# SCH_usb-usb_2025-03-20.net
KiCad netlist of a schematic drawn in EasyEDA
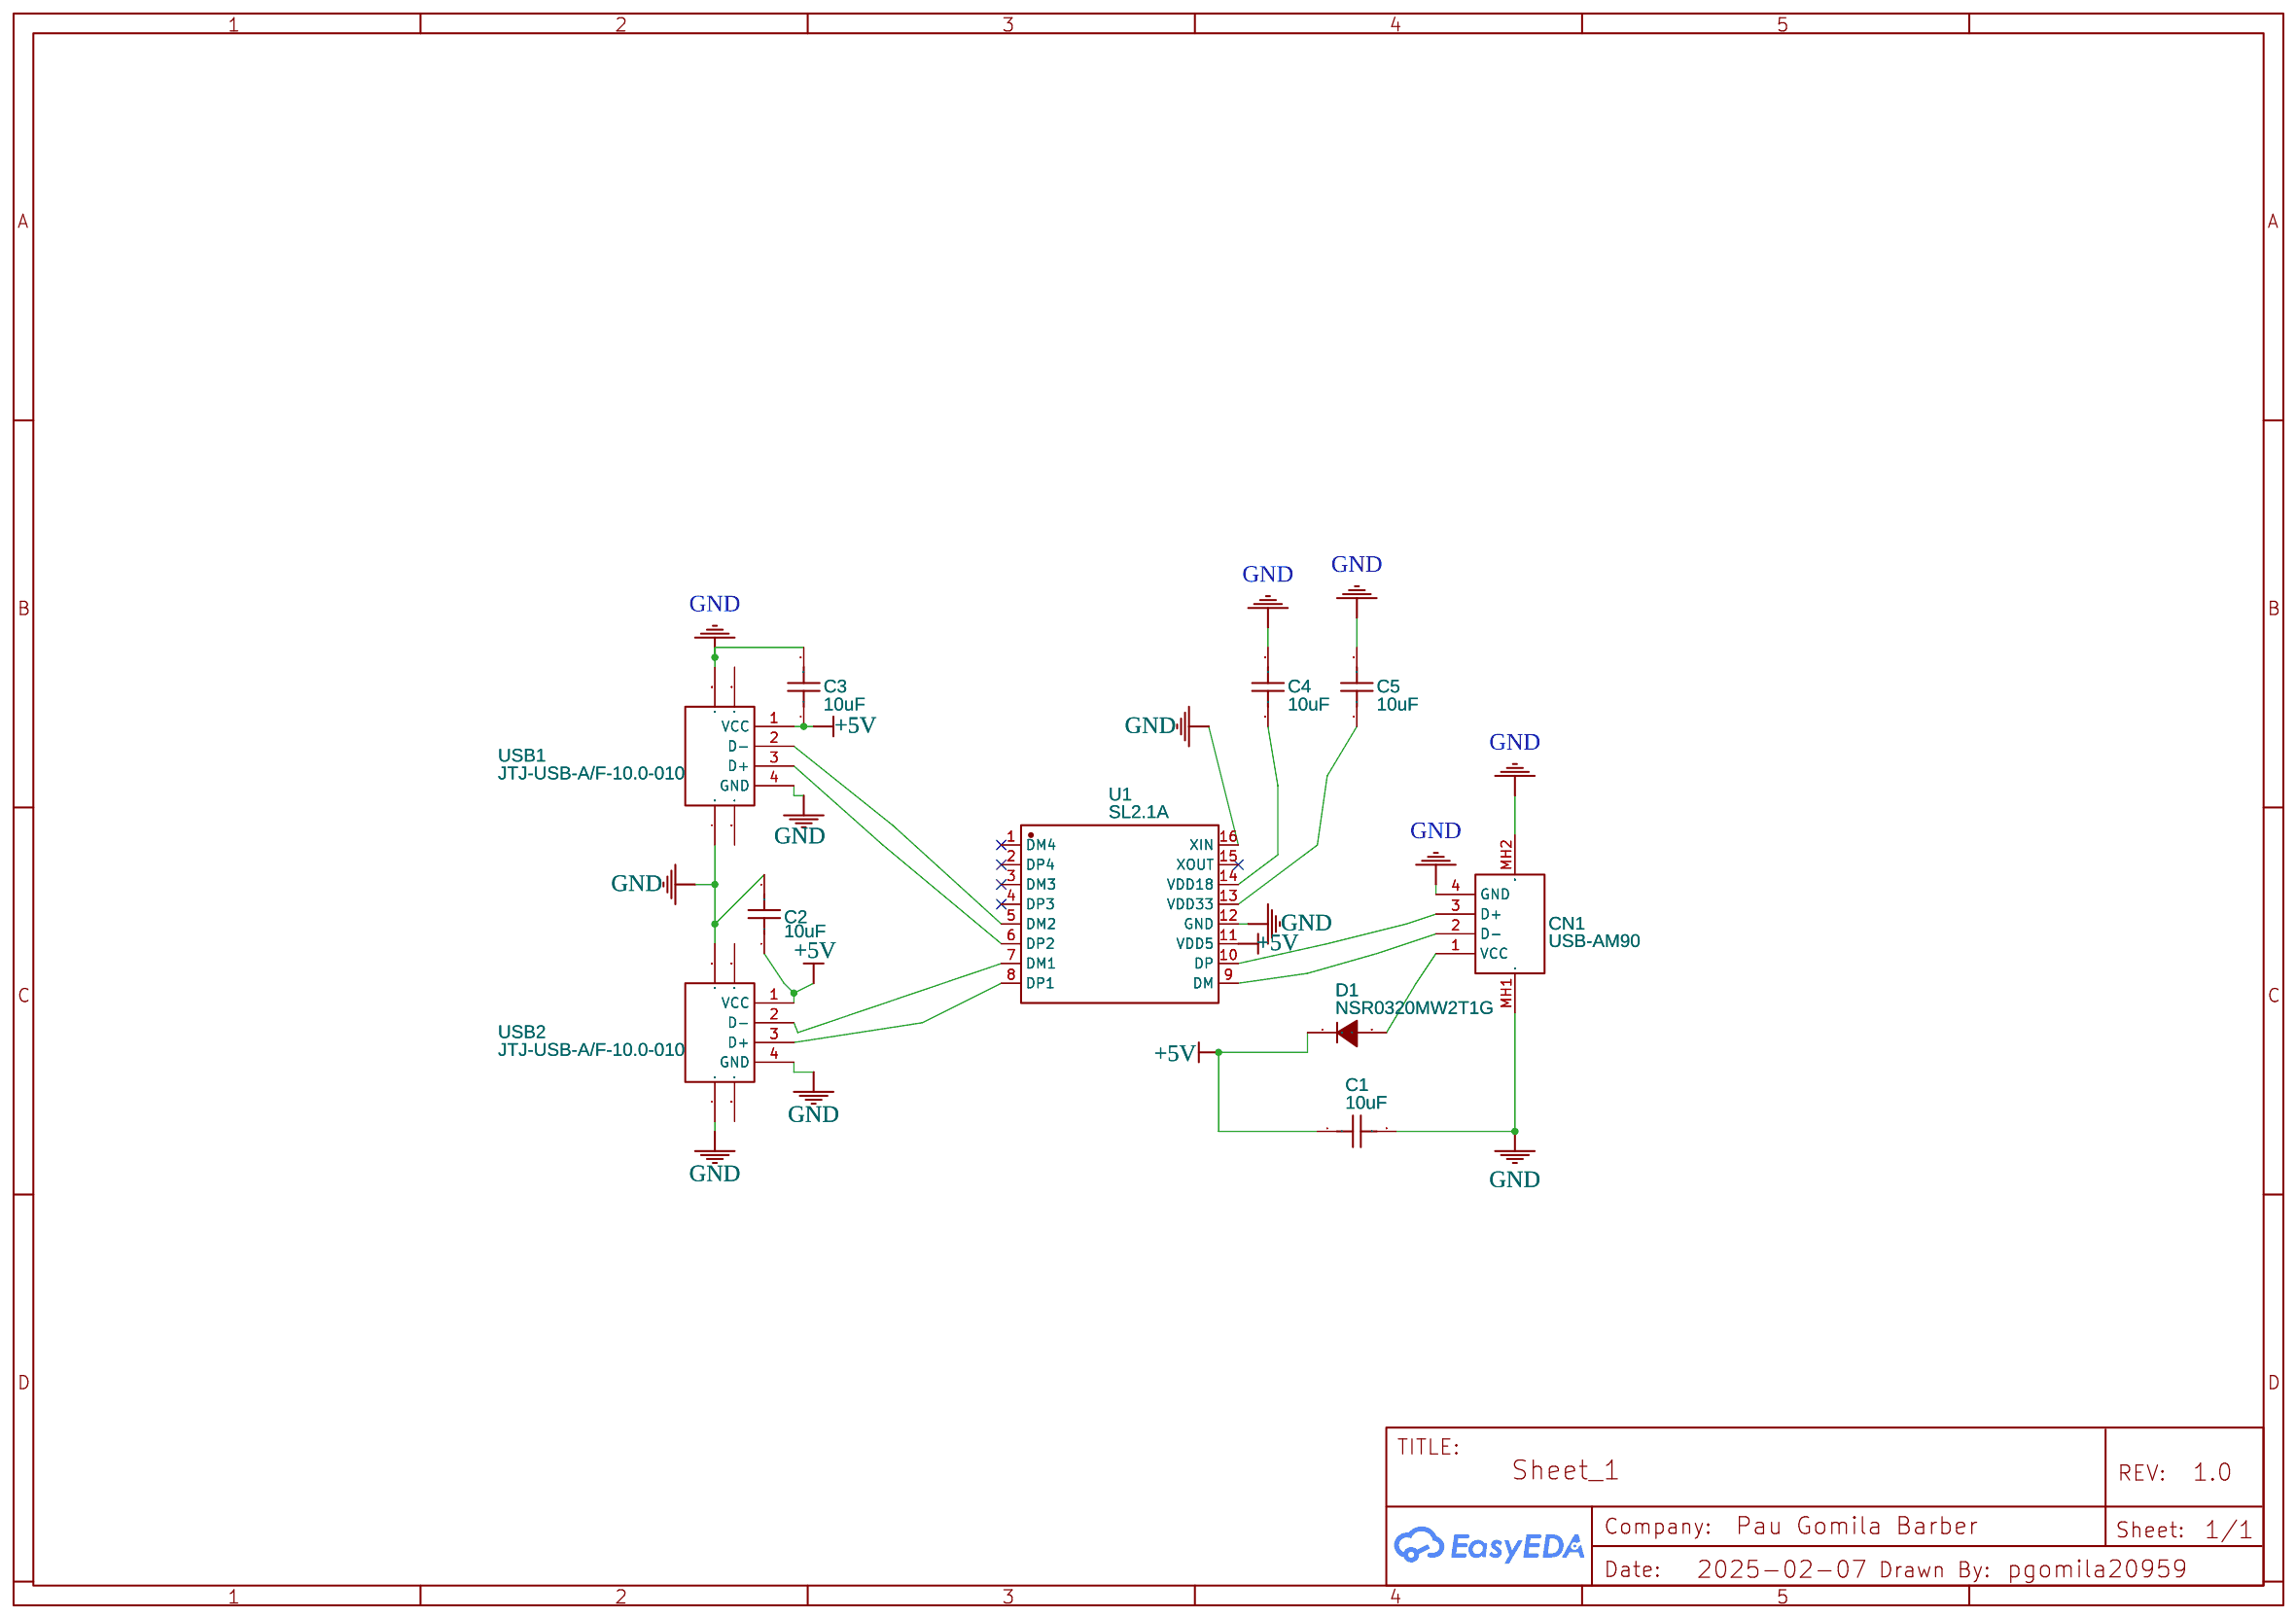
[diagram p0: schematic sheet]

(export (version "E")
  (design (tool "Eeschema 10.0.6"))
  (components
    (comp (ref "C1")
      (value "10uF")
      (fields
        (field (name "Manufacturer Part") "CL10A106KP8NNNC")
        (field (name "Manufacturer") "SAMSUNG(三星)")
      )
      (libsource (lib "") (part "CL10A106KP8NNNC_1"))
    )
    (comp (ref "C2")
      (value "10uF")
      (fields
        (field (name "Manufacturer Part") "CL10A106KP8NNNC")
        (field (name "Manufacturer") "SAMSUNG(三星)")
      )
      (libsource (lib "") (part "CL10A106KP8NNNC"))
    )
    (comp (ref "C3")
      (value "10uF")
      (fields
        (field (name "Manufacturer Part") "CL10A106KP8NNNC")
        (field (name "Manufacturer") "SAMSUNG(三星)")
      )
      (libsource (lib "") (part "CL10A106KP8NNNC"))
    )
    (comp (ref "C4")
      (value "10uF")
      (fields
        (field (name "Manufacturer Part") "CL10A106KP8NNNC")
        (field (name "Manufacturer") "SAMSUNG(三星)")
      )
      (libsource (lib "") (part "CL10A106KP8NNNC"))
    )
    (comp (ref "C5")
      (value "10uF")
      (fields
        (field (name "Manufacturer Part") "CL10A106KP8NNNC")
        (field (name "Manufacturer") "SAMSUNG(三星)")
      )
      (libsource (lib "") (part "CL10A106KP8NNNC"))
    )
    (comp (ref "CN1")
      (value "USB-AM90")
      (fields (field (name "Manufacturer") "ValuePro"))
      (libsource (lib "") (part "USB-AM90"))
    )
    (comp (ref "D1")
      (value "NSR0320MW2T1G")
      (fields (field (name "Manufacturer") "onsemi(安森美)"))
      (libsource (lib "") (part "NSR0320MW2T1G"))
    )
    (comp (ref "U1")
      (value "SL2.1A")
      (fields (field (name "Manufacturer") "CoreChips(和芯润德)"))
      (libsource (lib "") (part "SL2.1A"))
    )
    (comp (ref "USB1")
      (value "JTJ-USB-A/F-10.0-010")
      (fields (field (name "Manufacturer Part") "908-371A1011D10100") (field (name "Manufacturer") "精拓金"))
      (libsource (lib "") (part "JTJ-USB-A/F-10.0-010"))
    )
    (comp (ref "USB2")
      (value "JTJ-USB-A/F-10.0-010")
      (fields (field (name "Manufacturer Part") "908-371A1011D10100") (field (name "Manufacturer") "精拓金"))
      (libsource (lib "") (part "JTJ-USB-A/F-10.0-010"))
    )
  )
  (nets
    (net (code "1") (name "+5V") (class "Default")
      (node (ref "C1") (pin "1") (pinfunction "1_1") (pintype "unspecified"))
      (node (ref "C2") (pin "1") (pinfunction "1_1") (pintype "unspecified"))
      (node (ref "C3") (pin "1") (pinfunction "1_1") (pintype "unspecified"))
      (node (ref "D1") (pin "1") (pinfunction "C_1") (pintype "unspecified"))
      (node (ref "U1") (pin "11") (pinfunction "VDD5_11") (pintype "unspecified"))
      (node (ref "USB1") (pin "1") (pinfunction "VCC_1") (pintype "input"))
      (node (ref "USB2") (pin "1") (pinfunction "VCC_1") (pintype "input"))
    )
    (net (code "2") (name "GND") (class "Default")
      (node (ref "C1") (pin "2") (pinfunction "2_2") (pintype "unspecified"))
      (node (ref "C2") (pin "2") (pinfunction "2_2") (pintype "unspecified"))
      (node (ref "C3") (pin "2") (pinfunction "2_2") (pintype "unspecified"))
      (node (ref "C4") (pin "2") (pinfunction "2_2") (pintype "unspecified"))
      (node (ref "C5") (pin "2") (pinfunction "2_2") (pintype "unspecified"))
      (node (ref "CN1") (pin "4") (pinfunction "GND_4") (pintype "input"))
      (node (ref "CN1") (pin "MH1") (pinfunction "MH1_MH1") (pintype "unspecified"))
      (node (ref "CN1") (pin "MH2") (pinfunction "MH2_MH2") (pintype "unspecified"))
      (node (ref "U1") (pin "12") (pinfunction "GND_12") (pintype "unspecified"))
      (node (ref "U1") (pin "16") (pinfunction "XIN_16") (pintype "unspecified"))
      (node (ref "USB1") (pin "4") (pinfunction "GND_4") (pintype "input"))
      (node (ref "USB1") (pin "6") (pinfunction "0_6") (pintype "unspecified"))
      (node (ref "USB1") (pin "7") (pinfunction "0_7") (pintype "unspecified"))
      (node (ref "USB2") (pin "4") (pinfunction "GND_4") (pintype "input"))
      (node (ref "USB2") (pin "6") (pinfunction "0_6") (pintype "unspecified"))
      (node (ref "USB2") (pin "7") (pinfunction "0_7") (pintype "unspecified"))
    )
    (net (code "3") (name "Net-(CN1-D+)") (class "Default")
      (node (ref "CN1") (pin "3") (pinfunction "D+_3") (pintype "input"))
      (node (ref "U1") (pin "10") (pinfunction "DP_10") (pintype "unspecified"))
    )
    (net (code "4") (name "Net-(CN1-D-)") (class "Default")
      (node (ref "CN1") (pin "2") (pinfunction "D-_2") (pintype "input"))
      (node (ref "U1") (pin "9") (pinfunction "DM_9") (pintype "unspecified"))
    )
    (net (code "5") (name "Net-(CN1-VCC)") (class "Default")
      (node (ref "CN1") (pin "1") (pinfunction "VCC_1") (pintype "input"))
      (node (ref "D1") (pin "2") (pinfunction "A_2") (pintype "unspecified"))
    )
    (net (code "6") (name "Net-(U1-DM1)") (class "Default")
      (node (ref "U1") (pin "7") (pinfunction "DM1_7") (pintype "unspecified"))
      (node (ref "USB2") (pin "2") (pinfunction "D-_2") (pintype "input"))
    )
    (net (code "7") (name "Net-(U1-DM2)") (class "Default")
      (node (ref "U1") (pin "5") (pinfunction "DM2_5") (pintype "unspecified"))
      (node (ref "USB1") (pin "2") (pinfunction "D-_2") (pintype "input"))
    )
    (net (code "8") (name "Net-(U1-DP1)") (class "Default")
      (node (ref "U1") (pin "8") (pinfunction "DP1_8") (pintype "unspecified"))
      (node (ref "USB2") (pin "3") (pinfunction "D+_3") (pintype "input"))
    )
    (net (code "9") (name "Net-(U1-DP2)") (class "Default")
      (node (ref "U1") (pin "6") (pinfunction "DP2_6") (pintype "unspecified"))
      (node (ref "USB1") (pin "3") (pinfunction "D+_3") (pintype "input"))
    )
    (net (code "10") (name "Net-(U1-VDD18)") (class "Default")
      (node (ref "C4") (pin "1") (pinfunction "1_1") (pintype "unspecified"))
      (node (ref "U1") (pin "14") (pinfunction "VDD18_14") (pintype "unspecified"))
    )
    (net (code "11") (name "Net-(U1-VDD33)") (class "Default")
      (node (ref "C5") (pin "1") (pinfunction "1_1") (pintype "unspecified"))
      (node (ref "U1") (pin "13") (pinfunction "VDD33_13") (pintype "unspecified"))
    )
    (net (code "12") (name "unconnected-(U1-DM3-Pad3)") (class "Default")
      (node (ref "U1") (pin "3") (pinfunction "DM3_3") (pintype "unspecified+no_connect"))
    )
    (net (code "13") (name "unconnected-(U1-DM4-Pad1)") (class "Default")
      (node (ref "U1") (pin "1") (pinfunction "DM4_1") (pintype "unspecified+no_connect"))
    )
    (net (code "14") (name "unconnected-(U1-DP3-Pad4)") (class "Default")
      (node (ref "U1") (pin "4") (pinfunction "DP3_4") (pintype "unspecified+no_connect"))
    )
    (net (code "15") (name "unconnected-(U1-DP4-Pad2)") (class "Default")
      (node (ref "U1") (pin "2") (pinfunction "DP4_2") (pintype "unspecified+no_connect"))
    )
    (net (code "16") (name "unconnected-(U1-XOUT-Pad15)") (class "Default")
      (node (ref "U1") (pin "15") (pinfunction "XOUT_15") (pintype "unspecified+no_connect"))
    )
    (net (code "17") (name "unconnected-(USB1-0-Pad5)") (class "Default")
      (node (ref "USB1") (pin "5") (pinfunction "0_5") (pintype "unspecified"))
    )
    (net (code "18") (name "unconnected-(USB1-0-Pad8)") (class "Default")
      (node (ref "USB1") (pin "8") (pinfunction "0_8") (pintype "unspecified"))
    )
    (net (code "19") (name "unconnected-(USB2-0-Pad5)") (class "Default")
      (node (ref "USB2") (pin "5") (pinfunction "0_5") (pintype "unspecified"))
    )
    (net (code "20") (name "unconnected-(USB2-0-Pad8)") (class "Default")
      (node (ref "USB2") (pin "8") (pinfunction "0_8") (pintype "unspecified"))
    )
  )
)
